# p04_buttons.net
KiCad netlist of a schematic drawn in Altium Designer
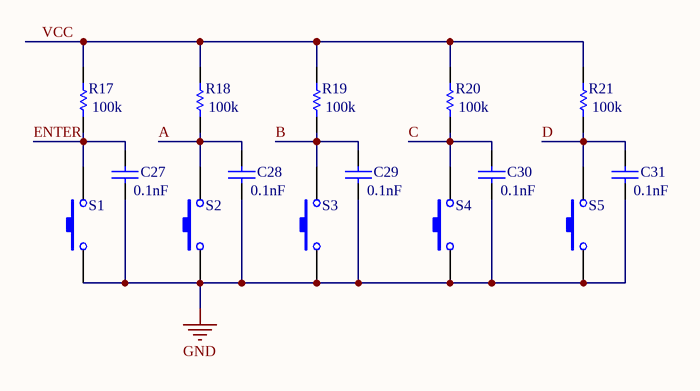
[diagram p0: p04_buttons.SchDoc]

(export (version "E")
  (design (tool "Eeschema 10.0.6"))
  (components
    (comp (ref "C27")
      (value "0.1nF")
      (footprint "Miscellaneous Devices:C0805")
      (description "Capacitor")
      (fields (field (name "Comment") "Cap") (field (name "PUBLISHER") "Altium Limited"))
      (libsource (lib "Miscellaneous Devices") (part "Cap"))
    )
    (comp (ref "C28")
      (value "0.1nF")
      (footprint "Miscellaneous Devices:C0805")
      (description "Capacitor")
      (fields (field (name "Comment") "Cap") (field (name "PUBLISHER") "Altium Limited"))
      (libsource (lib "Miscellaneous Devices") (part "Cap"))
    )
    (comp (ref "C29")
      (value "0.1nF")
      (footprint "Miscellaneous Devices:C0805")
      (description "Capacitor")
      (fields (field (name "Comment") "Cap") (field (name "PUBLISHER") "Altium Limited"))
      (libsource (lib "Miscellaneous Devices") (part "Cap"))
    )
    (comp (ref "C30")
      (value "0.1nF")
      (footprint "Miscellaneous Devices:C0805")
      (description "Capacitor")
      (fields (field (name "Comment") "Cap") (field (name "PUBLISHER") "Altium Limited"))
      (libsource (lib "Miscellaneous Devices") (part "Cap"))
    )
    (comp (ref "C31")
      (value "0.1nF")
      (footprint "Miscellaneous Devices:C0805")
      (description "Capacitor")
      (fields (field (name "Comment") "Cap") (field (name "PUBLISHER") "Altium Limited"))
      (libsource (lib "Miscellaneous Devices") (part "Cap"))
    )
    (comp (ref "R17")
      (value "100k")
      (footprint "6-0805_M")
      (description "Resistor")
      (fields (field (name "Comment") "Res1") (field (name "PUBLISHER") "Altium Limited"))
      (libsource (lib "Miscellaneous Devices") (part "Res1"))
    )
    (comp (ref "R18")
      (value "100k")
      (footprint "6-0805_M")
      (description "Resistor")
      (fields (field (name "Comment") "Res1") (field (name "PUBLISHER") "Altium Limited"))
      (libsource (lib "Miscellaneous Devices") (part "Res1"))
    )
    (comp (ref "R19")
      (value "100k")
      (footprint "6-0805_M")
      (description "Resistor")
      (fields (field (name "Comment") "Res1") (field (name "PUBLISHER") "Altium Limited"))
      (libsource (lib "Miscellaneous Devices") (part "Res1"))
    )
    (comp (ref "R20")
      (value "100k")
      (footprint "6-0805_M")
      (description "Resistor")
      (fields (field (name "Comment") "Res1") (field (name "PUBLISHER") "Altium Limited"))
      (libsource (lib "Miscellaneous Devices") (part "Res1"))
    )
    (comp (ref "R21")
      (value "100k")
      (footprint "6-0805_M")
      (description "Resistor")
      (fields (field (name "Comment") "Res1") (field (name "PUBLISHER") "Altium Limited"))
      (libsource (lib "Miscellaneous Devices") (part "Res1"))
    )
    (comp (ref "S1")
      (value "SW-PB")
      (footprint "SPST-2")
      (description "Switch")
      (fields (field (name "PUBLISHER") "Altium Limited"))
      (libsource (lib "Miscellaneous Devices") (part "SW-PB"))
    )
    (comp (ref "S2")
      (value "SW-PB")
      (footprint "SPST-2")
      (description "Switch")
      (fields (field (name "PUBLISHER") "Altium Limited"))
      (libsource (lib "Miscellaneous Devices") (part "SW-PB"))
    )
    (comp (ref "S3")
      (value "SW-PB")
      (footprint "SPST-2")
      (description "Switch")
      (fields (field (name "PUBLISHER") "Altium Limited"))
      (libsource (lib "Miscellaneous Devices") (part "SW-PB"))
    )
    (comp (ref "S4")
      (value "SW-PB")
      (footprint "SPST-2")
      (description "Switch")
      (fields (field (name "PUBLISHER") "Altium Limited"))
      (libsource (lib "Miscellaneous Devices") (part "SW-PB"))
    )
    (comp (ref "S5")
      (value "SW-PB")
      (footprint "SPST-2")
      (description "Switch")
      (fields (field (name "PUBLISHER") "Altium Limited"))
      (libsource (lib "Miscellaneous Devices") (part "SW-PB"))
    )
  )
  (nets
    (net (code "1") (name "/A") (class "Default")
      (node (ref "C28") (pin "1") (pinfunction "1_1") (pintype "passive"))
      (node (ref "R18") (pin "2") (pinfunction "2_2") (pintype "passive"))
      (node (ref "S2") (pin "2") (pinfunction "2_2") (pintype "passive"))
    )
    (net (code "2") (name "/B") (class "Default")
      (node (ref "C29") (pin "1") (pinfunction "1_1") (pintype "passive"))
      (node (ref "R19") (pin "2") (pinfunction "2_2") (pintype "passive"))
      (node (ref "S3") (pin "2") (pinfunction "2_2") (pintype "passive"))
    )
    (net (code "3") (name "/C") (class "Default")
      (node (ref "C30") (pin "1") (pinfunction "1_1") (pintype "passive"))
      (node (ref "R20") (pin "2") (pinfunction "2_2") (pintype "passive"))
      (node (ref "S4") (pin "2") (pinfunction "2_2") (pintype "passive"))
    )
    (net (code "4") (name "/D") (class "Default")
      (node (ref "C31") (pin "1") (pinfunction "1_1") (pintype "passive"))
      (node (ref "R21") (pin "2") (pinfunction "2_2") (pintype "passive"))
      (node (ref "S5") (pin "2") (pinfunction "2_2") (pintype "passive"))
    )
    (net (code "5") (name "/ENTER") (class "Default")
      (node (ref "C27") (pin "1") (pinfunction "1_1") (pintype "passive"))
      (node (ref "R17") (pin "2") (pinfunction "2_2") (pintype "passive"))
      (node (ref "S1") (pin "2") (pinfunction "2_2") (pintype "passive"))
    )
    (net (code "6") (name "/VCC") (class "Default")
      (node (ref "R17") (pin "1") (pinfunction "1_1") (pintype "passive"))
      (node (ref "R18") (pin "1") (pinfunction "1_1") (pintype "passive"))
      (node (ref "R19") (pin "1") (pinfunction "1_1") (pintype "passive"))
      (node (ref "R20") (pin "1") (pinfunction "1_1") (pintype "passive"))
      (node (ref "R21") (pin "1") (pinfunction "1_1") (pintype "passive"))
    )
    (net (code "7") (name "GND") (class "Default")
      (node (ref "C27") (pin "2") (pinfunction "2_2") (pintype "passive"))
      (node (ref "C28") (pin "2") (pinfunction "2_2") (pintype "passive"))
      (node (ref "C29") (pin "2") (pinfunction "2_2") (pintype "passive"))
      (node (ref "C30") (pin "2") (pinfunction "2_2") (pintype "passive"))
      (node (ref "C31") (pin "2") (pinfunction "2_2") (pintype "passive"))
      (node (ref "S1") (pin "1") (pinfunction "1_1") (pintype "passive"))
      (node (ref "S2") (pin "1") (pinfunction "1_1") (pintype "passive"))
      (node (ref "S3") (pin "1") (pinfunction "1_1") (pintype "passive"))
      (node (ref "S4") (pin "1") (pinfunction "1_1") (pintype "passive"))
      (node (ref "S5") (pin "1") (pinfunction "1_1") (pintype "passive"))
    )
  )
)
